# Schematics.net
KiCad netlist of a schematic drawn in EAGLE
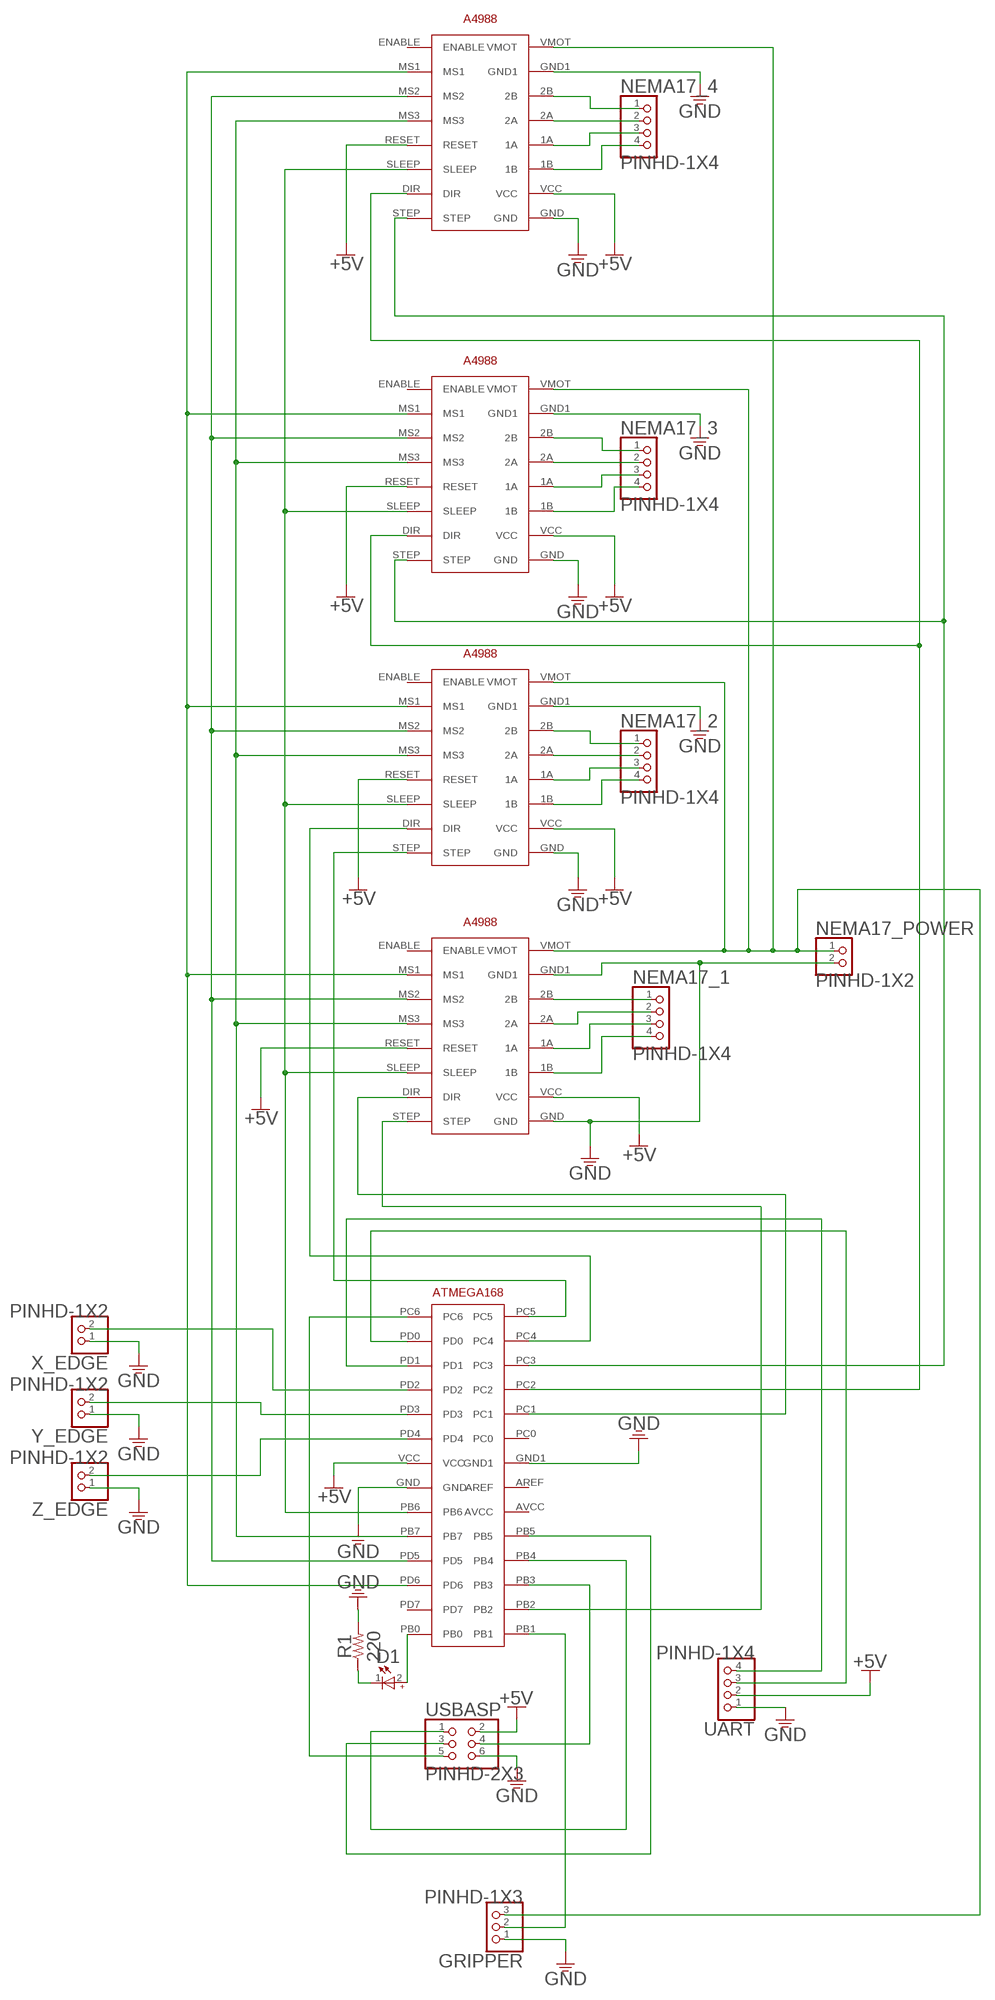
[diagram p0: schematic, sheet 1]

(export (version "E")
  (design (tool "Eeschema 10.0.6"))
  (components
    (comp (ref "D1")
      (value "151033BS03000")
      (footprint "eagle-import:WL-TMRW_3MM_STOPPER")
      (libsource (lib "eagle-import") (part "WL-TMRW_3MM_WITHSTOPPER_151033BS03000"))
    )
    (comp (ref "GRIPPER")
      (value "PINHD-1X3")
      (footprint "eagle-import:1X03")
      (libsource (lib "eagle-import") (part "PINHD-1X3"))
    )
    (comp (ref "NEMA17_1")
      (value "PINHD-1X4")
      (footprint "eagle-import:1X04")
      (libsource (lib "eagle-import") (part "PINHD-1X4"))
    )
    (comp (ref "NEMA17_2")
      (value "PINHD-1X4")
      (footprint "eagle-import:1X04")
      (libsource (lib "eagle-import") (part "PINHD-1X4"))
    )
    (comp (ref "NEMA17_3")
      (value "PINHD-1X4")
      (footprint "eagle-import:1X04")
      (libsource (lib "eagle-import") (part "PINHD-1X4"))
    )
    (comp (ref "NEMA17_4")
      (value "PINHD-1X4")
      (footprint "eagle-import:1X04")
      (libsource (lib "eagle-import") (part "PINHD-1X4"))
    )
    (comp (ref "NEMA17_POWER")
      (value "PINHD-1X2")
      (footprint "eagle-import:1X02")
      (libsource (lib "eagle-import") (part "PINHD-1X2"))
    )
    (comp (ref "R1")
      (value "220")
      (footprint "eagle-import:RESAD724W46L381D178B")
      (libsource (lib "eagle-import") (part "R-USAXIAL-7.2MM-PITCH_"))
    )
    (comp (ref "U$1")
      (value "ATMEGA168")
      (footprint "eagle-import:ATMEGA168FOOTPRINT")
      (libsource (lib "eagle-import") (part "ATMEGA168"))
    )
    (comp (ref "U$2")
      (value "A4988")
      (footprint "eagle-import:A498-FOOTPRINT")
      (libsource (lib "eagle-import") (part "A4988"))
    )
    (comp (ref "U$3")
      (value "A4988")
      (footprint "eagle-import:A498-FOOTPRINT")
      (libsource (lib "eagle-import") (part "A4988"))
    )
    (comp (ref "U$4")
      (value "A4988")
      (footprint "eagle-import:A498-FOOTPRINT")
      (libsource (lib "eagle-import") (part "A4988"))
    )
    (comp (ref "U$5")
      (value "A4988")
      (footprint "eagle-import:A498-FOOTPRINT")
      (libsource (lib "eagle-import") (part "A4988"))
    )
    (comp (ref "UART")
      (value "PINHD-1X4")
      (footprint "eagle-import:1X04")
      (libsource (lib "eagle-import") (part "PINHD-1X4"))
    )
    (comp (ref "USBASP")
      (value "PINHD-2X3")
      (footprint "eagle-import:2X03")
      (libsource (lib "eagle-import") (part "PINHD-2X3"))
    )
    (comp (ref "X_EDGE")
      (value "PINHD-1X2")
      (footprint "eagle-import:1X02")
      (libsource (lib "eagle-import") (part "PINHD-1X2"))
    )
    (comp (ref "Y_EDGE")
      (value "PINHD-1X2")
      (footprint "eagle-import:1X02")
      (libsource (lib "eagle-import") (part "PINHD-1X2"))
    )
    (comp (ref "Z_EDGE")
      (value "PINHD-1X2")
      (footprint "eagle-import:1X02")
      (libsource (lib "eagle-import") (part "PINHD-1X2"))
    )
  )
  (nets
    (net (code "1") (name "+5V") (class "Default")
      (node (ref "U$1") (pin "VCC") (pinfunction "VCC_VCC") (pintype "bidirectional"))
      (node (ref "U$2") (pin "RESET") (pinfunction "RESET_RESET") (pintype "bidirectional"))
      (node (ref "U$2") (pin "VCC") (pinfunction "VCC_VCC") (pintype "bidirectional"))
      (node (ref "U$3") (pin "RESET") (pinfunction "RESET_RESET") (pintype "bidirectional"))
      (node (ref "U$3") (pin "VCC") (pinfunction "VCC_VCC") (pintype "bidirectional"))
      (node (ref "U$4") (pin "RESET") (pinfunction "RESET_RESET") (pintype "bidirectional"))
      (node (ref "U$4") (pin "VCC") (pinfunction "VCC_VCC") (pintype "bidirectional"))
      (node (ref "U$5") (pin "RESET") (pinfunction "RESET_RESET") (pintype "bidirectional"))
      (node (ref "U$5") (pin "VCC") (pinfunction "VCC_VCC") (pintype "bidirectional"))
      (node (ref "UART") (pin "2") (pinfunction "2_2") (pintype "passive"))
      (node (ref "USBASP") (pin "2") (pinfunction "2_2") (pintype "passive"))
    )
    (net (code "2") (name "GND") (class "Default")
      (node (ref "GRIPPER") (pin "1") (pinfunction "1_1") (pintype "passive"))
      (node (ref "NEMA17_POWER") (pin "2") (pinfunction "2_2") (pintype "passive"))
      (node (ref "R1") (pin "2") (pinfunction "2_2") (pintype "passive"))
      (node (ref "U$1") (pin "GND") (pinfunction "GND_GND") (pintype "bidirectional"))
      (node (ref "U$1") (pin "GND1") (pinfunction "GND1_GND1") (pintype "bidirectional"))
      (node (ref "U$2") (pin "GND") (pinfunction "GND_GND") (pintype "bidirectional"))
      (node (ref "U$2") (pin "GND1") (pinfunction "GND1_GND1") (pintype "bidirectional"))
      (node (ref "U$3") (pin "GND") (pinfunction "GND_GND") (pintype "bidirectional"))
      (node (ref "U$3") (pin "GND1") (pinfunction "GND1_GND1") (pintype "bidirectional"))
      (node (ref "U$4") (pin "GND") (pinfunction "GND_GND") (pintype "bidirectional"))
      (node (ref "U$4") (pin "GND1") (pinfunction "GND1_GND1") (pintype "bidirectional"))
      (node (ref "U$5") (pin "GND") (pinfunction "GND_GND") (pintype "bidirectional"))
      (node (ref "U$5") (pin "GND1") (pinfunction "GND1_GND1") (pintype "bidirectional"))
      (node (ref "UART") (pin "1") (pinfunction "1_1") (pintype "passive"))
      (node (ref "USBASP") (pin "6") (pinfunction "6_6") (pintype "passive"))
      (node (ref "X_EDGE") (pin "1") (pinfunction "1_1") (pintype "passive"))
      (node (ref "Y_EDGE") (pin "1") (pinfunction "1_1") (pintype "passive"))
      (node (ref "Z_EDGE") (pin "1") (pinfunction "1_1") (pintype "passive"))
    )
    (net (code "3") (name "Net-(D1-+)") (class "Default")
      (node (ref "D1") (pin "2") (pinfunction "+_2") (pintype "passive"))
      (node (ref "U$1") (pin "PB0") (pinfunction "PB0_PB0") (pintype "bidirectional"))
    )
    (net (code "4") (name "Net-(D1--)") (class "Default")
      (node (ref "D1") (pin "1") (pinfunction "-_1") (pintype "passive"))
      (node (ref "R1") (pin "1") (pinfunction "1_1") (pintype "passive"))
    )
    (net (code "5") (name "Net-(GRIPPER-Pad2)") (class "Default")
      (node (ref "GRIPPER") (pin "2") (pinfunction "2_2") (pintype "passive"))
      (node (ref "U$1") (pin "PB1") (pinfunction "PB1_PB1") (pintype "bidirectional"))
    )
    (net (code "6") (name "Net-(GRIPPER-Pad3)") (class "Default")
      (node (ref "GRIPPER") (pin "3") (pinfunction "3_3") (pintype "passive"))
      (node (ref "NEMA17_POWER") (pin "1") (pinfunction "1_1") (pintype "passive"))
      (node (ref "U$2") (pin "VMOT") (pinfunction "VMOT_VMOT") (pintype "bidirectional"))
      (node (ref "U$3") (pin "VMOT") (pinfunction "VMOT_VMOT") (pintype "bidirectional"))
      (node (ref "U$4") (pin "VMOT") (pinfunction "VMOT_VMOT") (pintype "bidirectional"))
      (node (ref "U$5") (pin "VMOT") (pinfunction "VMOT_VMOT") (pintype "bidirectional"))
    )
    (net (code "7") (name "Net-(NEMA17_1-Pad1)") (class "Default")
      (node (ref "NEMA17_1") (pin "1") (pinfunction "1_1") (pintype "passive"))
      (node (ref "U$2") (pin "2B") (pinfunction "2B_2B") (pintype "bidirectional"))
    )
    (net (code "8") (name "Net-(NEMA17_1-Pad2)") (class "Default")
      (node (ref "NEMA17_1") (pin "2") (pinfunction "2_2") (pintype "passive"))
      (node (ref "U$2") (pin "2A") (pinfunction "2A_2A") (pintype "bidirectional"))
    )
    (net (code "9") (name "Net-(NEMA17_1-Pad3)") (class "Default")
      (node (ref "NEMA17_1") (pin "3") (pinfunction "3_3") (pintype "passive"))
      (node (ref "U$2") (pin "1A") (pinfunction "1A_1A") (pintype "bidirectional"))
    )
    (net (code "10") (name "Net-(NEMA17_1-Pad4)") (class "Default")
      (node (ref "NEMA17_1") (pin "4") (pinfunction "4_4") (pintype "passive"))
      (node (ref "U$2") (pin "1B") (pinfunction "1B_1B") (pintype "bidirectional"))
    )
    (net (code "11") (name "Net-(NEMA17_2-Pad1)") (class "Default")
      (node (ref "NEMA17_2") (pin "1") (pinfunction "1_1") (pintype "passive"))
      (node (ref "U$3") (pin "2B") (pinfunction "2B_2B") (pintype "bidirectional"))
    )
    (net (code "12") (name "Net-(NEMA17_2-Pad2)") (class "Default")
      (node (ref "NEMA17_2") (pin "2") (pinfunction "2_2") (pintype "passive"))
      (node (ref "U$3") (pin "2A") (pinfunction "2A_2A") (pintype "bidirectional"))
    )
    (net (code "13") (name "Net-(NEMA17_2-Pad3)") (class "Default")
      (node (ref "NEMA17_2") (pin "3") (pinfunction "3_3") (pintype "passive"))
      (node (ref "U$3") (pin "1A") (pinfunction "1A_1A") (pintype "bidirectional"))
    )
    (net (code "14") (name "Net-(NEMA17_2-Pad4)") (class "Default")
      (node (ref "NEMA17_2") (pin "4") (pinfunction "4_4") (pintype "passive"))
      (node (ref "U$3") (pin "1B") (pinfunction "1B_1B") (pintype "bidirectional"))
    )
    (net (code "15") (name "Net-(NEMA17_3-Pad1)") (class "Default")
      (node (ref "NEMA17_3") (pin "1") (pinfunction "1_1") (pintype "passive"))
      (node (ref "U$4") (pin "2B") (pinfunction "2B_2B") (pintype "bidirectional"))
    )
    (net (code "16") (name "Net-(NEMA17_3-Pad2)") (class "Default")
      (node (ref "NEMA17_3") (pin "2") (pinfunction "2_2") (pintype "passive"))
      (node (ref "U$4") (pin "2A") (pinfunction "2A_2A") (pintype "bidirectional"))
    )
    (net (code "17") (name "Net-(NEMA17_3-Pad3)") (class "Default")
      (node (ref "NEMA17_3") (pin "3") (pinfunction "3_3") (pintype "passive"))
      (node (ref "U$4") (pin "1A") (pinfunction "1A_1A") (pintype "bidirectional"))
    )
    (net (code "18") (name "Net-(NEMA17_3-Pad4)") (class "Default")
      (node (ref "NEMA17_3") (pin "4") (pinfunction "4_4") (pintype "passive"))
      (node (ref "U$4") (pin "1B") (pinfunction "1B_1B") (pintype "bidirectional"))
    )
    (net (code "19") (name "Net-(NEMA17_4-Pad1)") (class "Default")
      (node (ref "NEMA17_4") (pin "1") (pinfunction "1_1") (pintype "passive"))
      (node (ref "U$5") (pin "2B") (pinfunction "2B_2B") (pintype "bidirectional"))
    )
    (net (code "20") (name "Net-(NEMA17_4-Pad2)") (class "Default")
      (node (ref "NEMA17_4") (pin "2") (pinfunction "2_2") (pintype "passive"))
      (node (ref "U$5") (pin "2A") (pinfunction "2A_2A") (pintype "bidirectional"))
    )
    (net (code "21") (name "Net-(NEMA17_4-Pad3)") (class "Default")
      (node (ref "NEMA17_4") (pin "3") (pinfunction "3_3") (pintype "passive"))
      (node (ref "U$5") (pin "1A") (pinfunction "1A_1A") (pintype "bidirectional"))
    )
    (net (code "22") (name "Net-(NEMA17_4-Pad4)") (class "Default")
      (node (ref "NEMA17_4") (pin "4") (pinfunction "4_4") (pintype "passive"))
      (node (ref "U$5") (pin "1B") (pinfunction "1B_1B") (pintype "bidirectional"))
    )
    (net (code "23") (name "Net-(U$1-PadPB2)") (class "Default")
      (node (ref "U$1") (pin "PB2") (pinfunction "PB2_PB2") (pintype "bidirectional"))
      (node (ref "U$2") (pin "STEP") (pinfunction "STEP_STEP") (pintype "bidirectional"))
    )
    (net (code "24") (name "Net-(U$1-PadPB3)") (class "Default")
      (node (ref "U$1") (pin "PB3") (pinfunction "PB3_PB3") (pintype "bidirectional"))
      (node (ref "USBASP") (pin "4") (pinfunction "4_4") (pintype "passive"))
    )
    (net (code "25") (name "Net-(U$1-PadPB4)") (class "Default")
      (node (ref "U$1") (pin "PB4") (pinfunction "PB4_PB4") (pintype "bidirectional"))
      (node (ref "USBASP") (pin "1") (pinfunction "1_1") (pintype "passive"))
    )
    (net (code "26") (name "Net-(U$1-PadPB5)") (class "Default")
      (node (ref "U$1") (pin "PB5") (pinfunction "PB5_PB5") (pintype "bidirectional"))
      (node (ref "USBASP") (pin "3") (pinfunction "3_3") (pintype "passive"))
    )
    (net (code "27") (name "Net-(U$1-PadPB6)") (class "Default")
      (node (ref "U$1") (pin "PB6") (pinfunction "PB6_PB6") (pintype "bidirectional"))
      (node (ref "U$2") (pin "SLEEP") (pinfunction "SLEEP_SLEEP") (pintype "bidirectional"))
      (node (ref "U$3") (pin "SLEEP") (pinfunction "SLEEP_SLEEP") (pintype "bidirectional"))
      (node (ref "U$4") (pin "SLEEP") (pinfunction "SLEEP_SLEEP") (pintype "bidirectional"))
      (node (ref "U$5") (pin "SLEEP") (pinfunction "SLEEP_SLEEP") (pintype "bidirectional"))
    )
    (net (code "28") (name "Net-(U$1-PadPB7)") (class "Default")
      (node (ref "U$1") (pin "PB7") (pinfunction "PB7_PB7") (pintype "bidirectional"))
      (node (ref "U$2") (pin "MS3") (pinfunction "MS3_MS3") (pintype "bidirectional"))
      (node (ref "U$3") (pin "MS3") (pinfunction "MS3_MS3") (pintype "bidirectional"))
      (node (ref "U$4") (pin "MS3") (pinfunction "MS3_MS3") (pintype "bidirectional"))
      (node (ref "U$5") (pin "MS3") (pinfunction "MS3_MS3") (pintype "bidirectional"))
    )
    (net (code "29") (name "Net-(U$1-PadPC1)") (class "Default")
      (node (ref "U$1") (pin "PC1") (pinfunction "PC1_PC1") (pintype "bidirectional"))
      (node (ref "U$2") (pin "DIR") (pinfunction "DIR_DIR") (pintype "bidirectional"))
    )
    (net (code "30") (name "Net-(U$1-PadPC2)") (class "Default")
      (node (ref "U$1") (pin "PC2") (pinfunction "PC2_PC2") (pintype "bidirectional"))
      (node (ref "U$4") (pin "DIR") (pinfunction "DIR_DIR") (pintype "bidirectional"))
      (node (ref "U$5") (pin "DIR") (pinfunction "DIR_DIR") (pintype "bidirectional"))
    )
    (net (code "31") (name "Net-(U$1-PadPC3)") (class "Default")
      (node (ref "U$1") (pin "PC3") (pinfunction "PC3_PC3") (pintype "bidirectional"))
      (node (ref "U$4") (pin "STEP") (pinfunction "STEP_STEP") (pintype "bidirectional"))
      (node (ref "U$5") (pin "STEP") (pinfunction "STEP_STEP") (pintype "bidirectional"))
    )
    (net (code "32") (name "Net-(U$1-PadPC4)") (class "Default")
      (node (ref "U$1") (pin "PC4") (pinfunction "PC4_PC4") (pintype "bidirectional"))
      (node (ref "U$3") (pin "DIR") (pinfunction "DIR_DIR") (pintype "bidirectional"))
    )
    (net (code "33") (name "Net-(U$1-PadPC5)") (class "Default")
      (node (ref "U$1") (pin "PC5") (pinfunction "PC5_PC5") (pintype "bidirectional"))
      (node (ref "U$3") (pin "STEP") (pinfunction "STEP_STEP") (pintype "bidirectional"))
    )
    (net (code "34") (name "Net-(U$1-PadPC6)") (class "Default")
      (node (ref "U$1") (pin "PC6") (pinfunction "PC6_PC6") (pintype "bidirectional"))
      (node (ref "USBASP") (pin "5") (pinfunction "5_5") (pintype "passive"))
    )
    (net (code "35") (name "Net-(U$1-PadPD0)") (class "Default")
      (node (ref "U$1") (pin "PD0") (pinfunction "PD0_PD0") (pintype "bidirectional"))
      (node (ref "UART") (pin "3") (pinfunction "3_3") (pintype "passive"))
    )
    (net (code "36") (name "Net-(U$1-PadPD1)") (class "Default")
      (node (ref "U$1") (pin "PD1") (pinfunction "PD1_PD1") (pintype "bidirectional"))
      (node (ref "UART") (pin "4") (pinfunction "4_4") (pintype "passive"))
    )
    (net (code "37") (name "Net-(U$1-PadPD2)") (class "Default")
      (node (ref "U$1") (pin "PD2") (pinfunction "PD2_PD2") (pintype "bidirectional"))
      (node (ref "X_EDGE") (pin "2") (pinfunction "2_2") (pintype "passive"))
    )
    (net (code "38") (name "Net-(U$1-PadPD3)") (class "Default")
      (node (ref "U$1") (pin "PD3") (pinfunction "PD3_PD3") (pintype "bidirectional"))
      (node (ref "Y_EDGE") (pin "2") (pinfunction "2_2") (pintype "passive"))
    )
    (net (code "39") (name "Net-(U$1-PadPD4)") (class "Default")
      (node (ref "U$1") (pin "PD4") (pinfunction "PD4_PD4") (pintype "bidirectional"))
      (node (ref "Z_EDGE") (pin "2") (pinfunction "2_2") (pintype "passive"))
    )
    (net (code "40") (name "Net-(U$1-PadPD5)") (class "Default")
      (node (ref "U$1") (pin "PD5") (pinfunction "PD5_PD5") (pintype "bidirectional"))
      (node (ref "U$2") (pin "MS2") (pinfunction "MS2_MS2") (pintype "bidirectional"))
      (node (ref "U$3") (pin "MS2") (pinfunction "MS2_MS2") (pintype "bidirectional"))
      (node (ref "U$4") (pin "MS2") (pinfunction "MS2_MS2") (pintype "bidirectional"))
      (node (ref "U$5") (pin "MS2") (pinfunction "MS2_MS2") (pintype "bidirectional"))
    )
    (net (code "41") (name "Net-(U$1-PadPD6)") (class "Default")
      (node (ref "U$1") (pin "PD6") (pinfunction "PD6_PD6") (pintype "bidirectional"))
      (node (ref "U$2") (pin "MS1") (pinfunction "MS1_MS1") (pintype "bidirectional"))
      (node (ref "U$3") (pin "MS1") (pinfunction "MS1_MS1") (pintype "bidirectional"))
      (node (ref "U$4") (pin "MS1") (pinfunction "MS1_MS1") (pintype "bidirectional"))
      (node (ref "U$5") (pin "MS1") (pinfunction "MS1_MS1") (pintype "bidirectional"))
    )
    (net (code "42") (name "unconnected-(U$1-PadAREF)") (class "Default")
      (node (ref "U$1") (pin "AREF") (pinfunction "AREF_AREF") (pintype "bidirectional"))
    )
    (net (code "43") (name "unconnected-(U$1-PadAVCC)") (class "Default")
      (node (ref "U$1") (pin "AVCC") (pinfunction "AVCC_AVCC") (pintype "bidirectional"))
    )
    (net (code "44") (name "unconnected-(U$1-PadPC0)") (class "Default")
      (node (ref "U$1") (pin "PC0") (pinfunction "PC0_PC0") (pintype "bidirectional"))
    )
    (net (code "45") (name "unconnected-(U$1-PadPD7)") (class "Default")
      (node (ref "U$1") (pin "PD7") (pinfunction "PD7_PD7") (pintype "bidirectional"))
    )
    (net (code "46") (name "unconnected-(U$2-PadENABLE)") (class "Default")
      (node (ref "U$2") (pin "ENABLE") (pinfunction "ENABLE_ENABLE") (pintype "bidirectional"))
    )
    (net (code "47") (name "unconnected-(U$3-PadENABLE)") (class "Default")
      (node (ref "U$3") (pin "ENABLE") (pinfunction "ENABLE_ENABLE") (pintype "bidirectional"))
    )
    (net (code "48") (name "unconnected-(U$4-PadENABLE)") (class "Default")
      (node (ref "U$4") (pin "ENABLE") (pinfunction "ENABLE_ENABLE") (pintype "bidirectional"))
    )
    (net (code "49") (name "unconnected-(U$5-PadENABLE)") (class "Default")
      (node (ref "U$5") (pin "ENABLE") (pinfunction "ENABLE_ENABLE") (pintype "bidirectional"))
    )
  )
)
